# Peripherals.net
KiCad netlist of a schematic drawn in Altium Designer
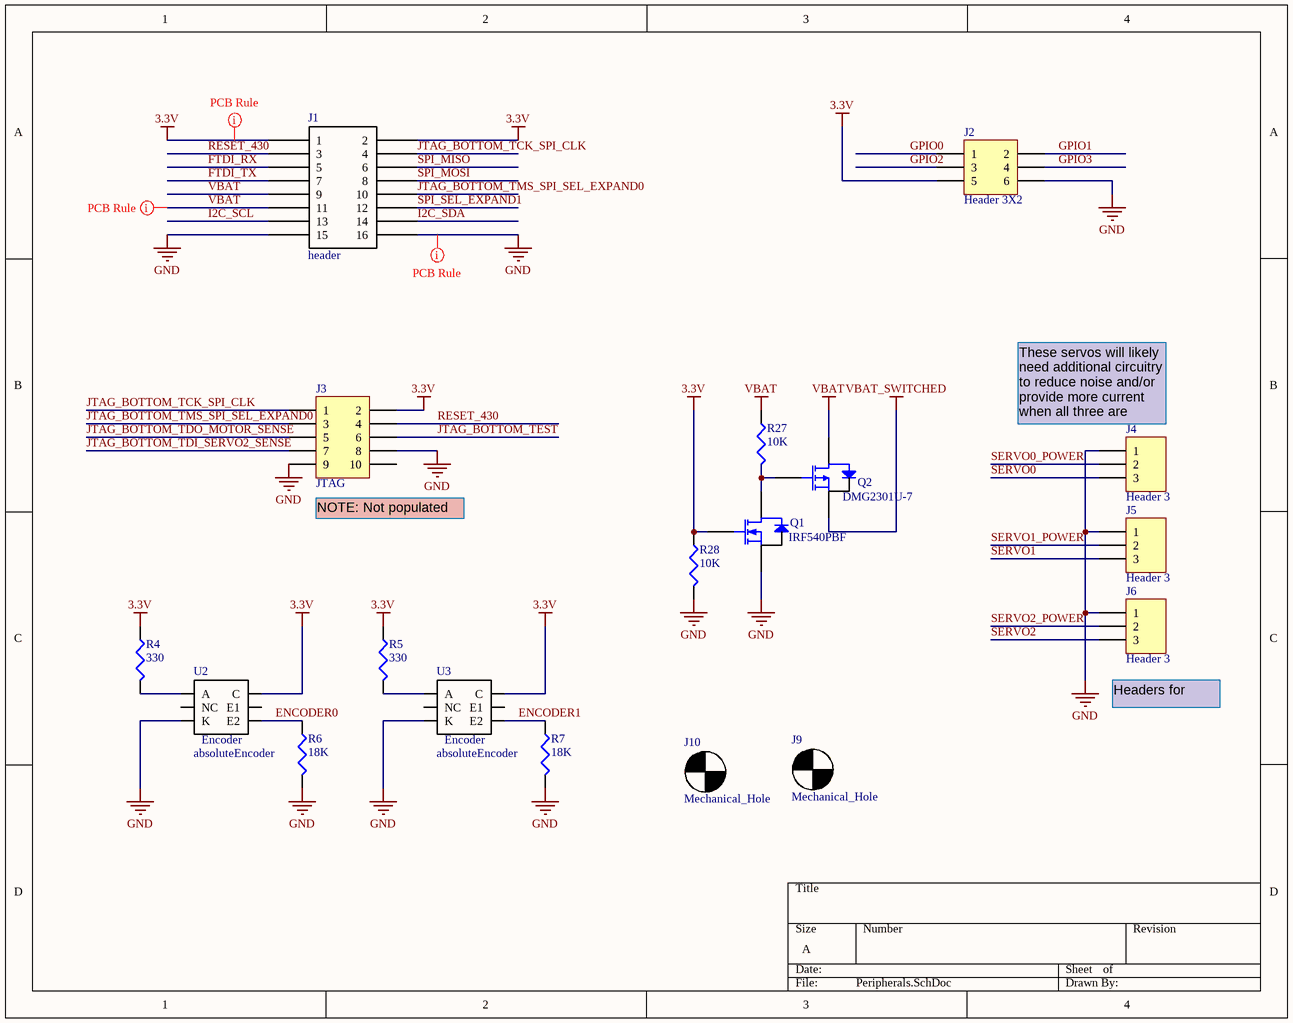
[diagram p0: Peripherals.SchDoc]

(export (version "E")
  (design (tool "Eeschema 10.0.6"))
  (components
    (comp (ref "J1")
      (value "header")
      (footprint "HEADERSM 8X2")
      (libsource (lib "mrone") (part "HEADER 8X2"))
    )
    (comp (ref "J2")
      (value "Header 3X2")
      (footprint "HDR2X3")
      (description "Header, 3-Pin, Dual row")
      (fields (field (name "PUBLISHER") "Altium Limited"))
      (libsource (lib "mrone") (part "Header 3X2"))
    )
    (comp (ref "J3")
      (value "JTAG")
      (footprint "HDR2X5")
      (description "Header, 5-Pin, Dual row")
      (fields (field (name "PUBLISHER") "Altium Limited"))
      (libsource (lib "Miscellaneous Connectors") (part "Header 5X2"))
    )
    (comp (ref "J4")
      (value "Header 3")
      (footprint "HDR1X3")
      (description "Header, 3-Pin")
      (fields (field (name "PUBLISHER") "Altium Limited"))
      (libsource (lib "mrone") (part "Header 3"))
    )
    (comp (ref "J5")
      (value "Header 3")
      (footprint "HDR1X3")
      (description "Header, 3-Pin")
      (fields (field (name "PUBLISHER") "Altium Limited"))
      (libsource (lib "mrone") (part "Header 3"))
    )
    (comp (ref "J6")
      (value "Header 3")
      (footprint "HDR1X3")
      (description "Header, 3-Pin")
      (fields (field (name "PUBLISHER") "Altium Limited"))
      (libsource (lib "mrone") (part "Header 3"))
    )
    (comp (ref "J9")
      (value "Mechanical_Hole")
      (footprint "#4_Screw_Hole")
      (description "A mechanical hole for mounting the board")
      (libsource (lib "mrone") (part "Mechanical_Hole"))
    )
    (comp (ref "J10")
      (value "Mechanical_Hole")
      (footprint "#4_Screw_Hole")
      (description "A mechanical hole for mounting the board")
      (libsource (lib "mrone") (part "Mechanical_Hole"))
    )
    (comp (ref "Q1") (value "IRF540PBF") (footprint "SOT-23") (libsource (lib "mrone") (part "N-Mosfet")))
    (comp (ref "Q2") (value "DMG2301U-7") (footprint "SOT-23") (libsource (lib "mrone") (part "P-Mosfet")))
    (comp (ref "R4")
      (value "330")
      (footprint "J1-0603")
      (description "Resistor")
      (fields (field (name "Comment") "A") (field (name "PUBLISHER") "Altium Limited"))
      (libsource (lib "Miscellaneous Devices") (part "Res3"))
    )
    (comp (ref "R5")
      (value "330")
      (footprint "J1-0603")
      (description "Resistor")
      (fields (field (name "Comment") "A") (field (name "PUBLISHER") "Altium Limited"))
      (libsource (lib "Miscellaneous Devices") (part "Res3"))
    )
    (comp (ref "R6")
      (value "18K")
      (footprint "J1-0603")
      (description "Resistor")
      (fields (field (name "Comment") "E2") (field (name "PUBLISHER") "Altium Limited"))
      (libsource (lib "Miscellaneous Devices") (part "Res3"))
    )
    (comp (ref "R7")
      (value "18K")
      (footprint "J1-0603")
      (description "Resistor")
      (fields (field (name "Comment") "E2") (field (name "PUBLISHER") "Altium Limited"))
      (libsource (lib "Miscellaneous Devices") (part "Res3"))
    )
    (comp (ref "R27")
      (value "10K")
      (footprint "J1-0603")
      (description "Resistor")
      (fields (field (name "PUBLISHER") "Altium Limited"))
      (libsource (lib "Miscellaneous Devices") (part "Res3"))
    )
    (comp (ref "R28")
      (value "10K")
      (footprint "J1-0603")
      (description "Resistor")
      (fields (field (name "PUBLISHER") "Altium Limited"))
      (libsource (lib "Miscellaneous Devices") (part "Res3"))
    )
    (comp (ref "U2")
      (value "absoluteEncoder")
      (footprint "absoluteEncoder")
      (libsource (lib "mrone") (part "absoluteEncoder"))
    )
    (comp (ref "U3")
      (value "absoluteEncoder")
      (footprint "absoluteEncoder")
      (libsource (lib "mrone") (part "absoluteEncoder"))
    )
  )
  (nets
    (net (code "1") (name "/ENCODER0") (class "Default")
      (node (ref "R6") (pin "1") (pinfunction "1_1") (pintype "passive"))
      (node (ref "U2") (pin "E2") (pinfunction "E2_E2") (pintype "passive"))
    )
    (net (code "2") (name "/ENCODER1") (class "Default")
      (node (ref "R7") (pin "1") (pinfunction "1_1") (pintype "passive"))
      (node (ref "U3") (pin "E2") (pinfunction "E2_E2") (pintype "passive"))
    )
    (net (code "3") (name "/FTDI_RX") (class "Default")
      (node (ref "J1") (pin "5") (pinfunction "5_5") (pintype "passive"))
    )
    (net (code "4") (name "/FTDI_TX") (class "Default")
      (node (ref "J1") (pin "7") (pinfunction "7_7") (pintype "passive"))
    )
    (net (code "5") (name "/GPIO0") (class "Default")
      (node (ref "J2") (pin "1") (pinfunction "1_1") (pintype "passive"))
    )
    (net (code "6") (name "/GPIO1") (class "Default")
      (node (ref "J2") (pin "2") (pinfunction "2_2") (pintype "passive"))
    )
    (net (code "7") (name "/GPIO2") (class "Default")
      (node (ref "J2") (pin "3") (pinfunction "3_3") (pintype "passive"))
    )
    (net (code "8") (name "/GPIO3") (class "Default")
      (node (ref "J2") (pin "4") (pinfunction "4_4") (pintype "passive"))
    )
    (net (code "9") (name "/I2C_SCL") (class "Default")
      (node (ref "J1") (pin "13") (pinfunction "13_13") (pintype "passive"))
    )
    (net (code "10") (name "/I2C_SDA") (class "Default")
      (node (ref "J1") (pin "14") (pinfunction "14_14") (pintype "passive"))
    )
    (net (code "11") (name "/JTAG_BOTTOM_TCK_SPI_CLK") (class "Default")
      (node (ref "J1") (pin "4") (pinfunction "4_4") (pintype "passive"))
      (node (ref "J3") (pin "1") (pinfunction "1_1") (pintype "passive"))
    )
    (net (code "12") (name "/JTAG_BOTTOM_TDI_SERVO2_SENSE") (class "Default")
      (node (ref "J3") (pin "7") (pinfunction "7_7") (pintype "passive"))
    )
    (net (code "13") (name "/JTAG_BOTTOM_TDO_MOTOR_SENSE") (class "Default")
      (node (ref "J3") (pin "5") (pinfunction "5_5") (pintype "passive"))
    )
    (net (code "14") (name "/JTAG_BOTTOM_TEST") (class "Default")
      (node (ref "J3") (pin "6") (pinfunction "6_6") (pintype "passive"))
    )
    (net (code "15") (name "/JTAG_BOTTOM_TMS_SPI_SEL_EXPAND0") (class "Default")
      (node (ref "J1") (pin "10") (pinfunction "10_10") (pintype "passive"))
      (node (ref "J3") (pin "3") (pinfunction "3_3") (pintype "passive"))
    )
    (net (code "16") (name "/RESET_430") (class "Default")
      (node (ref "J1") (pin "3") (pinfunction "3_3") (pintype "passive"))
      (node (ref "J3") (pin "4") (pinfunction "4_4") (pintype "passive"))
    )
    (net (code "17") (name "/SERVO0") (class "Default")
      (node (ref "J4") (pin "3") (pinfunction "3_3") (pintype "passive"))
    )
    (net (code "18") (name "/SERVO0_POWER") (class "Default")
      (node (ref "J4") (pin "2") (pinfunction "2_2") (pintype "passive"))
    )
    (net (code "19") (name "/SERVO1") (class "Default")
      (node (ref "J5") (pin "3") (pinfunction "3_3") (pintype "passive"))
    )
    (net (code "20") (name "/SERVO1_POWER") (class "Default")
      (node (ref "J5") (pin "2") (pinfunction "2_2") (pintype "passive"))
    )
    (net (code "21") (name "/SERVO2") (class "Default")
      (node (ref "J6") (pin "3") (pinfunction "3_3") (pintype "passive"))
    )
    (net (code "22") (name "/SERVO2_POWER") (class "Default")
      (node (ref "J6") (pin "2") (pinfunction "2_2") (pintype "passive"))
    )
    (net (code "23") (name "/SPI_MISO") (class "Default")
      (node (ref "J1") (pin "6") (pinfunction "6_6") (pintype "passive"))
    )
    (net (code "24") (name "/SPI_MOSI") (class "Default")
      (node (ref "J1") (pin "8") (pinfunction "8_8") (pintype "passive"))
    )
    (net (code "25") (name "/SPI_SEL_EXPAND1") (class "Default")
      (node (ref "J1") (pin "12") (pinfunction "12_12") (pintype "passive"))
    )
    (net (code "26") (name "3.3V") (class "Default")
      (node (ref "J1") (pin "1") (pinfunction "1_1") (pintype "passive"))
      (node (ref "J1") (pin "2") (pinfunction "2_2") (pintype "passive"))
      (node (ref "J2") (pin "5") (pinfunction "5_5") (pintype "passive"))
      (node (ref "J3") (pin "2") (pinfunction "2_2") (pintype "passive"))
      (node (ref "Q1") (pin "1") (pinfunction "G_1") (pintype "passive"))
      (node (ref "R28") (pin "1") (pinfunction "1_1") (pintype "passive"))
      (node (ref "R4") (pin "1") (pinfunction "1_1") (pintype "passive"))
      (node (ref "R5") (pin "1") (pinfunction "1_1") (pintype "passive"))
      (node (ref "U2") (pin "C") (pinfunction "C_C") (pintype "passive"))
      (node (ref "U3") (pin "C") (pinfunction "C_C") (pintype "passive"))
    )
    (net (code "27") (name "GND") (class "Default")
      (node (ref "J1") (pin "15") (pinfunction "15_15") (pintype "passive"))
      (node (ref "J1") (pin "16") (pinfunction "16_16") (pintype "passive"))
      (node (ref "J2") (pin "6") (pinfunction "6_6") (pintype "passive"))
      (node (ref "J3") (pin "8") (pinfunction "8_8") (pintype "passive"))
      (node (ref "J3") (pin "9") (pinfunction "9_9") (pintype "passive"))
      (node (ref "J4") (pin "1") (pinfunction "1_1") (pintype "passive"))
      (node (ref "J5") (pin "1") (pinfunction "1_1") (pintype "passive"))
      (node (ref "J6") (pin "1") (pinfunction "1_1") (pintype "passive"))
      (node (ref "Q1") (pin "2") (pinfunction "S_2") (pintype "passive"))
      (node (ref "R28") (pin "2") (pinfunction "2_2") (pintype "passive"))
      (node (ref "R6") (pin "2") (pinfunction "2_2") (pintype "passive"))
      (node (ref "R7") (pin "2") (pinfunction "2_2") (pintype "passive"))
      (node (ref "U2") (pin "K") (pinfunction "K_K") (pintype "passive"))
      (node (ref "U3") (pin "K") (pinfunction "K_K") (pintype "passive"))
    )
    (net (code "28") (name "Net-(Q1-D)") (class "Default")
      (node (ref "Q1") (pin "3") (pinfunction "D_3") (pintype "passive"))
      (node (ref "Q2") (pin "1") (pinfunction "G_1") (pintype "passive"))
      (node (ref "R27") (pin "2") (pinfunction "2_2") (pintype "passive"))
    )
    (net (code "29") (name "Net-(R4-Pad2)") (class "Default")
      (node (ref "R4") (pin "2") (pinfunction "2_2") (pintype "passive"))
      (node (ref "U2") (pin "A") (pinfunction "A_A") (pintype "passive"))
    )
    (net (code "30") (name "Net-(R5-Pad2)") (class "Default")
      (node (ref "R5") (pin "2") (pinfunction "2_2") (pintype "passive"))
      (node (ref "U3") (pin "A") (pinfunction "A_A") (pintype "passive"))
    )
    (net (code "31") (name "VBAT") (class "Default")
      (node (ref "J1") (pin "11") (pinfunction "11_11") (pintype "passive"))
      (node (ref "J1") (pin "9") (pinfunction "9_9") (pintype "passive"))
      (node (ref "Q2") (pin "3") (pinfunction "D_3") (pintype "passive"))
      (node (ref "R27") (pin "1") (pinfunction "1_1") (pintype "passive"))
    )
    (net (code "32") (name "VBAT_SWITCHED") (class "Default")
      (node (ref "Q2") (pin "2") (pinfunction "S_2") (pintype "passive"))
    )
    (net (code "33") (name "unconnected-(J3-Pad10)") (class "Default")
      (node (ref "J3") (pin "10") (pinfunction "10_10") (pintype "passive"))
    )
    (net (code "34") (name "unconnected-(U2-PadE1)") (class "Default")
      (node (ref "U2") (pin "E1") (pinfunction "E1_E1") (pintype "passive"))
    )
    (net (code "35") (name "unconnected-(U2-PadNC)") (class "Default")
      (node (ref "U2") (pin "NC") (pinfunction "NC_NC") (pintype "passive"))
    )
    (net (code "36") (name "unconnected-(U3-PadE1)") (class "Default")
      (node (ref "U3") (pin "E1") (pinfunction "E1_E1") (pintype "passive"))
    )
    (net (code "37") (name "unconnected-(U3-PadNC)") (class "Default")
      (node (ref "U3") (pin "NC") (pinfunction "NC_NC") (pintype "passive"))
    )
  )
)
